# M2_KEY_M.net
KiCad netlist of a schematic drawn in Altium Designer
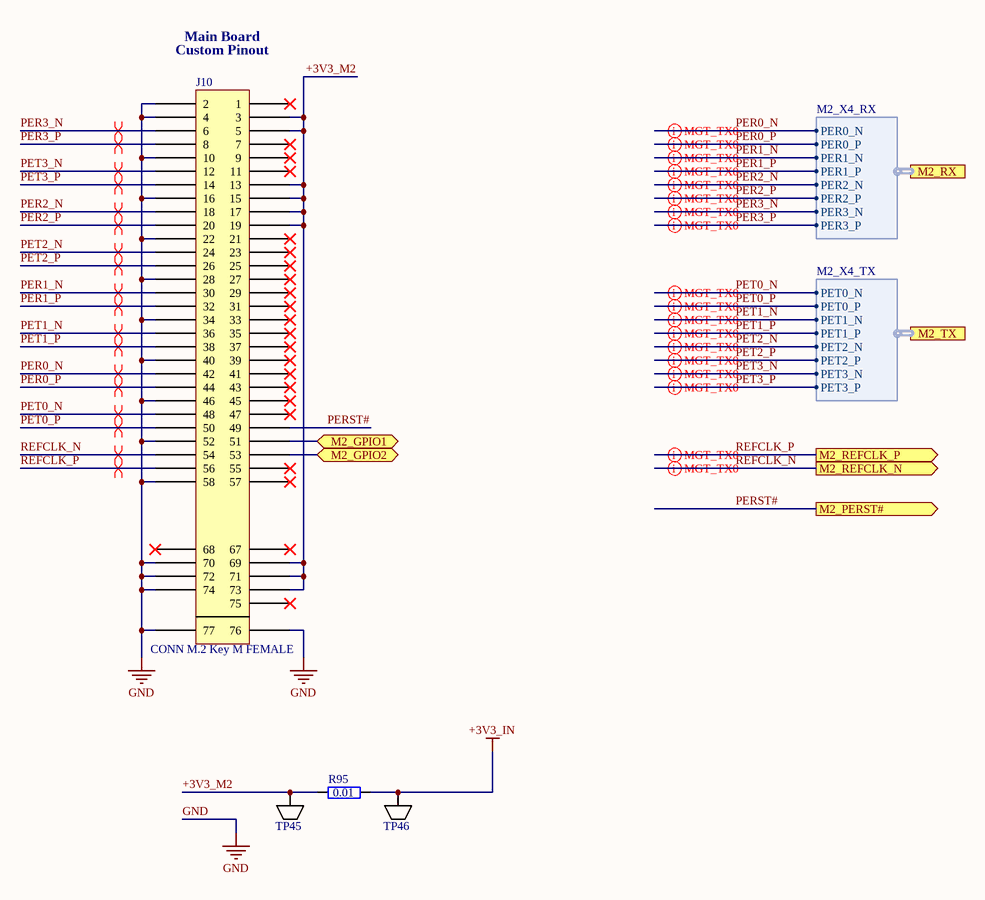
[diagram p0: M2_KEY_M.SchDoc]

(export (version "E")
  (design (tool "Eeschema 10.0.6"))
  (components
    (comp (ref "J10")
      (value "CONN M.2 Key M FEMALE")
      (footprint "TE_M2_KEYM_2199230")
      (libsource (lib "DSO") (part "CONN M.2 Key M FEMALE"))
    )
    (comp (ref "R95")
      (value "0.01")
      (footprint "GEN_R_0603")
      (fields (field (name "TOLERANCE") "1%"))
      (libsource (lib "DSO") (part "RES 0.01 OHM 1% 1/4W 0603"))
    )
    (comp (ref "TP45")
      (value "5015")
      (footprint "KEY_5015")
      (libsource (lib "DSO") (part "TP KEYSTONE 5015"))
    )
    (comp (ref "TP46")
      (value "5015")
      (footprint "KEY_5015")
      (libsource (lib "DSO") (part "TP KEYSTONE 5015"))
    )
  )
  (nets
    (net (code "3") (name "+3V3_IN") (class "Default")
      (node (ref "R95") (pin "2") (pinfunction "2_2") (pintype "passive"))
      (node (ref "TP46") (pin "1") (pinfunction "1_1") (pintype "passive"))
    )
    (net (code "4") (name "/+3V3_M2") (class "Default")
      (node (ref "J10") (pin "13") (pinfunction "13_13") (pintype "passive"))
      (node (ref "J10") (pin "15") (pinfunction "15_15") (pintype "passive"))
      (node (ref "J10") (pin "17") (pinfunction "17_17") (pintype "passive"))
      (node (ref "J10") (pin "19") (pinfunction "19_19") (pintype "passive"))
      (node (ref "J10") (pin "3") (pinfunction "3_3") (pintype "passive"))
      (node (ref "J10") (pin "5") (pinfunction "5_5") (pintype "passive"))
      (node (ref "J10") (pin "69") (pinfunction "69_69") (pintype "passive"))
      (node (ref "J10") (pin "71") (pinfunction "71_71") (pintype "passive"))
      (node (ref "J10") (pin "73") (pinfunction "73_73") (pintype "passive"))
      (node (ref "R95") (pin "1") (pinfunction "1_1") (pintype "passive"))
      (node (ref "TP45") (pin "1") (pinfunction "1_1") (pintype "passive"))
    )
    (net (code "5") (name "/M2_GPIO1") (class "Default")
      (node (ref "J10") (pin "51") (pinfunction "51_51") (pintype "passive"))
    )
    (net (code "6") (name "/M2_GPIO2") (class "Default")
      (node (ref "J10") (pin "53") (pinfunction "53_53") (pintype "passive"))
    )
    (net (code "7") (name "/PER0_N") (class "Default")
      (node (ref "J10") (pin "42") (pinfunction "42_42") (pintype "passive"))
    )
    (net (code "8") (name "/PER0_P") (class "Default")
      (node (ref "J10") (pin "44") (pinfunction "44_44") (pintype "passive"))
    )
    (net (code "9") (name "/PER1_N") (class "Default")
      (node (ref "J10") (pin "30") (pinfunction "30_30") (pintype "passive"))
    )
    (net (code "10") (name "/PER1_P") (class "Default")
      (node (ref "J10") (pin "32") (pinfunction "32_32") (pintype "passive"))
    )
    (net (code "11") (name "/PER2_N") (class "Default")
      (node (ref "J10") (pin "18") (pinfunction "18_18") (pintype "passive"))
    )
    (net (code "12") (name "/PER2_P") (class "Default")
      (node (ref "J10") (pin "20") (pinfunction "20_20") (pintype "passive"))
    )
    (net (code "13") (name "/PER3_N") (class "Default")
      (node (ref "J10") (pin "6") (pinfunction "6_6") (pintype "passive"))
    )
    (net (code "14") (name "/PER3_P") (class "Default")
      (node (ref "J10") (pin "8") (pinfunction "8_8") (pintype "passive"))
    )
    (net (code "15") (name "/PERST#") (class "Default")
      (node (ref "J10") (pin "49") (pinfunction "49_49") (pintype "passive"))
    )
    (net (code "16") (name "/PET0_N") (class "Default")
      (node (ref "J10") (pin "48") (pinfunction "48_48") (pintype "passive"))
    )
    (net (code "17") (name "/PET0_P") (class "Default")
      (node (ref "J10") (pin "50") (pinfunction "50_50") (pintype "passive"))
    )
    (net (code "18") (name "/PET1_N") (class "Default")
      (node (ref "J10") (pin "36") (pinfunction "36_36") (pintype "passive"))
    )
    (net (code "19") (name "/PET1_P") (class "Default")
      (node (ref "J10") (pin "38") (pinfunction "38_38") (pintype "passive"))
    )
    (net (code "20") (name "/PET2_N") (class "Default")
      (node (ref "J10") (pin "24") (pinfunction "24_24") (pintype "passive"))
    )
    (net (code "21") (name "/PET2_P") (class "Default")
      (node (ref "J10") (pin "26") (pinfunction "26_26") (pintype "passive"))
    )
    (net (code "22") (name "/PET3_N") (class "Default")
      (node (ref "J10") (pin "12") (pinfunction "12_12") (pintype "passive"))
    )
    (net (code "23") (name "/PET3_P") (class "Default")
      (node (ref "J10") (pin "14") (pinfunction "14_14") (pintype "passive"))
    )
    (net (code "24") (name "/REFCLK_N") (class "Default")
      (node (ref "J10") (pin "54") (pinfunction "54_54") (pintype "passive"))
    )
    (net (code "25") (name "/REFCLK_P") (class "Default")
      (node (ref "J10") (pin "56") (pinfunction "56_56") (pintype "passive"))
    )
    (net (code "28") (name "GND") (class "Default")
      (node (ref "J10") (pin "10") (pinfunction "10_10") (pintype "passive"))
      (node (ref "J10") (pin "16") (pinfunction "16_16") (pintype "passive"))
      (node (ref "J10") (pin "2") (pinfunction "2_2") (pintype "passive"))
      (node (ref "J10") (pin "22") (pinfunction "22_22") (pintype "passive"))
      (node (ref "J10") (pin "28") (pinfunction "28_28") (pintype "passive"))
      (node (ref "J10") (pin "34") (pinfunction "34_34") (pintype "passive"))
      (node (ref "J10") (pin "4") (pinfunction "4_4") (pintype "passive"))
      (node (ref "J10") (pin "40") (pinfunction "40_40") (pintype "passive"))
      (node (ref "J10") (pin "46") (pinfunction "46_46") (pintype "passive"))
      (node (ref "J10") (pin "52") (pinfunction "52_52") (pintype "passive"))
      (node (ref "J10") (pin "58") (pinfunction "58_58") (pintype "passive"))
      (node (ref "J10") (pin "70") (pinfunction "70_70") (pintype "passive"))
      (node (ref "J10") (pin "72") (pinfunction "72_72") (pintype "passive"))
      (node (ref "J10") (pin "74") (pinfunction "74_74") (pintype "passive"))
      (node (ref "J10") (pin "76") (pinfunction "76_76") (pintype "passive"))
      (node (ref "J10") (pin "77") (pinfunction "77_77") (pintype "passive"))
    )
    (net (code "29") (name "unconnected-(J10-Pad1)") (class "Default")
      (node (ref "J10") (pin "1") (pinfunction "1_1") (pintype "passive+no_connect"))
    )
    (net (code "30") (name "unconnected-(J10-Pad7)") (class "Default")
      (node (ref "J10") (pin "7") (pinfunction "7_7") (pintype "passive+no_connect"))
    )
    (net (code "31") (name "unconnected-(J10-Pad9)") (class "Default")
      (node (ref "J10") (pin "9") (pinfunction "9_9") (pintype "passive+no_connect"))
    )
    (net (code "32") (name "unconnected-(J10-Pad11)") (class "Default")
      (node (ref "J10") (pin "11") (pinfunction "11_11") (pintype "passive+no_connect"))
    )
    (net (code "33") (name "unconnected-(J10-Pad21)") (class "Default")
      (node (ref "J10") (pin "21") (pinfunction "21_21") (pintype "passive+no_connect"))
    )
    (net (code "34") (name "unconnected-(J10-Pad23)") (class "Default")
      (node (ref "J10") (pin "23") (pinfunction "23_23") (pintype "passive+no_connect"))
    )
    (net (code "35") (name "unconnected-(J10-Pad25)") (class "Default")
      (node (ref "J10") (pin "25") (pinfunction "25_25") (pintype "passive+no_connect"))
    )
    (net (code "36") (name "unconnected-(J10-Pad27)") (class "Default")
      (node (ref "J10") (pin "27") (pinfunction "27_27") (pintype "passive+no_connect"))
    )
    (net (code "37") (name "unconnected-(J10-Pad29)") (class "Default")
      (node (ref "J10") (pin "29") (pinfunction "29_29") (pintype "passive+no_connect"))
    )
    (net (code "38") (name "unconnected-(J10-Pad31)") (class "Default")
      (node (ref "J10") (pin "31") (pinfunction "31_31") (pintype "passive+no_connect"))
    )
    (net (code "39") (name "unconnected-(J10-Pad33)") (class "Default")
      (node (ref "J10") (pin "33") (pinfunction "33_33") (pintype "passive+no_connect"))
    )
    (net (code "40") (name "unconnected-(J10-Pad35)") (class "Default")
      (node (ref "J10") (pin "35") (pinfunction "35_35") (pintype "passive+no_connect"))
    )
    (net (code "41") (name "unconnected-(J10-Pad37)") (class "Default")
      (node (ref "J10") (pin "37") (pinfunction "37_37") (pintype "passive+no_connect"))
    )
    (net (code "42") (name "unconnected-(J10-Pad39)") (class "Default")
      (node (ref "J10") (pin "39") (pinfunction "39_39") (pintype "passive+no_connect"))
    )
    (net (code "43") (name "unconnected-(J10-Pad41)") (class "Default")
      (node (ref "J10") (pin "41") (pinfunction "41_41") (pintype "passive+no_connect"))
    )
    (net (code "44") (name "unconnected-(J10-Pad43)") (class "Default")
      (node (ref "J10") (pin "43") (pinfunction "43_43") (pintype "passive+no_connect"))
    )
    (net (code "45") (name "unconnected-(J10-Pad45)") (class "Default")
      (node (ref "J10") (pin "45") (pinfunction "45_45") (pintype "passive+no_connect"))
    )
    (net (code "46") (name "unconnected-(J10-Pad47)") (class "Default")
      (node (ref "J10") (pin "47") (pinfunction "47_47") (pintype "passive+no_connect"))
    )
    (net (code "47") (name "unconnected-(J10-Pad55)") (class "Default")
      (node (ref "J10") (pin "55") (pinfunction "55_55") (pintype "passive+no_connect"))
    )
    (net (code "48") (name "unconnected-(J10-Pad57)") (class "Default")
      (node (ref "J10") (pin "57") (pinfunction "57_57") (pintype "passive+no_connect"))
    )
    (net (code "49") (name "unconnected-(J10-Pad67)") (class "Default")
      (node (ref "J10") (pin "67") (pinfunction "67_67") (pintype "passive+no_connect"))
    )
    (net (code "50") (name "unconnected-(J10-Pad68)") (class "Default")
      (node (ref "J10") (pin "68") (pinfunction "68_68") (pintype "passive+no_connect"))
    )
    (net (code "51") (name "unconnected-(J10-Pad75)") (class "Default")
      (node (ref "J10") (pin "75") (pinfunction "75_75") (pintype "passive+no_connect"))
    )
  )
)
